# control-surface-right.net
KiCad netlist of a schematic drawn in EAGLE
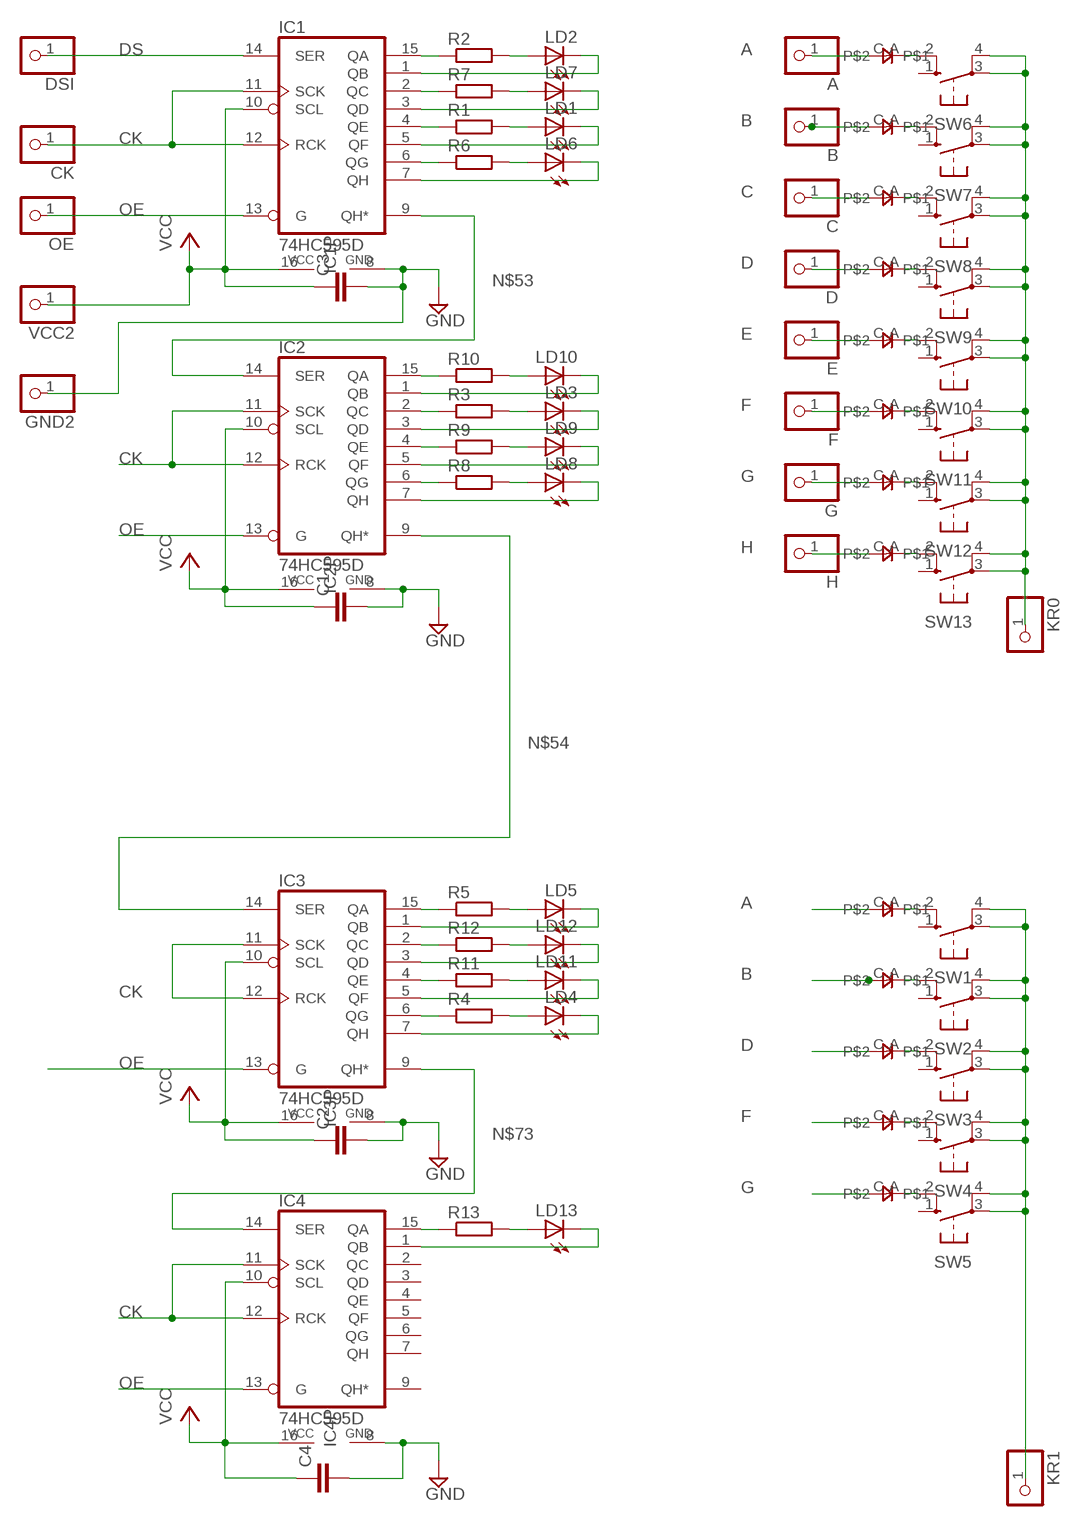
[diagram p0: schematic, sheet 1]

(export (version "E")
  (design (tool "Eeschema 10.0.6"))
  (components
    (comp (ref "A")
      (value "PINHD-1X1")
      (footprint "eagle-import:1X01")
      (libsource (lib "eagle-import") (part "PINHD-1X1"))
    )
    (comp (ref "B")
      (value "PINHD-1X1")
      (footprint "eagle-import:1X01")
      (libsource (lib "eagle-import") (part "PINHD-1X1"))
    )
    (comp (ref "C")
      (value "PINHD-1X1")
      (footprint "eagle-import:1X01")
      (libsource (lib "eagle-import") (part "PINHD-1X1"))
    )
    (comp (ref "C1")
      (value "C-EUC0805")
      (footprint "eagle-import:C0805")
      (libsource (lib "eagle-import") (part "C-EUC0805"))
    )
    (comp (ref "C2")
      (value "C-EUC0805")
      (footprint "eagle-import:C0805")
      (libsource (lib "eagle-import") (part "C-EUC0805"))
    )
    (comp (ref "C3")
      (value "C-EUC0805")
      (footprint "eagle-import:C0805")
      (libsource (lib "eagle-import") (part "C-EUC0805"))
    )
    (comp (ref "C4")
      (value "C-EUC0805")
      (footprint "eagle-import:C0805")
      (libsource (lib "eagle-import") (part "C-EUC0805"))
    )
    (comp (ref "CK")
      (value "PINHD-1X1")
      (footprint "eagle-import:1X01")
      (libsource (lib "eagle-import") (part "PINHD-1X1"))
    )
    (comp (ref "D")
      (value "PINHD-1X1")
      (footprint "eagle-import:1X01")
      (libsource (lib "eagle-import") (part "PINHD-1X1"))
    )
    (comp (ref "D1")
      (value "0805DIODE")
      (footprint "eagle-import:0805DIODE")
      (libsource (lib "eagle-import") (part "0805DIODE"))
    )
    (comp (ref "D2")
      (value "0805DIODE")
      (footprint "eagle-import:0805DIODE")
      (libsource (lib "eagle-import") (part "0805DIODE"))
    )
    (comp (ref "D3")
      (value "0805DIODE")
      (footprint "eagle-import:0805DIODE")
      (libsource (lib "eagle-import") (part "0805DIODE"))
    )
    (comp (ref "D4")
      (value "0805DIODE")
      (footprint "eagle-import:0805DIODE")
      (libsource (lib "eagle-import") (part "0805DIODE"))
    )
    (comp (ref "D5")
      (value "0805DIODE")
      (footprint "eagle-import:0805DIODE")
      (libsource (lib "eagle-import") (part "0805DIODE"))
    )
    (comp (ref "D6")
      (value "0805DIODE")
      (footprint "eagle-import:0805DIODE")
      (libsource (lib "eagle-import") (part "0805DIODE"))
    )
    (comp (ref "D7")
      (value "0805DIODE")
      (footprint "eagle-import:0805DIODE")
      (libsource (lib "eagle-import") (part "0805DIODE"))
    )
    (comp (ref "D8")
      (value "0805DIODE")
      (footprint "eagle-import:0805DIODE")
      (libsource (lib "eagle-import") (part "0805DIODE"))
    )
    (comp (ref "D9")
      (value "0805DIODE")
      (footprint "eagle-import:0805DIODE")
      (libsource (lib "eagle-import") (part "0805DIODE"))
    )
    (comp (ref "D10")
      (value "0805DIODE")
      (footprint "eagle-import:0805DIODE")
      (libsource (lib "eagle-import") (part "0805DIODE"))
    )
    (comp (ref "D11")
      (value "0805DIODE")
      (footprint "eagle-import:0805DIODE")
      (libsource (lib "eagle-import") (part "0805DIODE"))
    )
    (comp (ref "D12")
      (value "0805DIODE")
      (footprint "eagle-import:0805DIODE")
      (libsource (lib "eagle-import") (part "0805DIODE"))
    )
    (comp (ref "D13")
      (value "0805DIODE")
      (footprint "eagle-import:0805DIODE")
      (libsource (lib "eagle-import") (part "0805DIODE"))
    )
    (comp (ref "DSI")
      (value "PINHD-1X1")
      (footprint "eagle-import:1X01")
      (libsource (lib "eagle-import") (part "PINHD-1X1"))
    )
    (comp (ref "E")
      (value "PINHD-1X1")
      (footprint "eagle-import:1X01")
      (libsource (lib "eagle-import") (part "PINHD-1X1"))
    )
    (comp (ref "F")
      (value "PINHD-1X1")
      (footprint "eagle-import:1X01")
      (libsource (lib "eagle-import") (part "PINHD-1X1"))
    )
    (comp (ref "G")
      (value "PINHD-1X1")
      (footprint "eagle-import:1X01")
      (libsource (lib "eagle-import") (part "PINHD-1X1"))
    )
    (comp (ref "GND2")
      (value "PINHD-1X1")
      (footprint "eagle-import:1X01")
      (libsource (lib "eagle-import") (part "PINHD-1X1"))
    )
    (comp (ref "H")
      (value "PINHD-1X1")
      (footprint "eagle-import:1X01")
      (libsource (lib "eagle-import") (part "PINHD-1X1"))
    )
    (comp (ref "IC1")
      (value "74HC595D")
      (footprint "eagle-import:SO16")
      (libsource (lib "eagle-import") (part "74595DHC"))
    )
    (comp (ref "IC2")
      (value "74HC595D")
      (footprint "eagle-import:SO16")
      (libsource (lib "eagle-import") (part "74595DHC"))
    )
    (comp (ref "IC3")
      (value "74HC595D")
      (footprint "eagle-import:SO16")
      (libsource (lib "eagle-import") (part "74595DHC"))
    )
    (comp (ref "IC4")
      (value "74HC595D")
      (footprint "eagle-import:SO16")
      (libsource (lib "eagle-import") (part "74595DHC"))
    )
    (comp (ref "KR0")
      (value "PINHD-1X1")
      (footprint "eagle-import:1X01")
      (libsource (lib "eagle-import") (part "PINHD-1X1"))
    )
    (comp (ref "KR1")
      (value "PINHD-1X1")
      (footprint "eagle-import:1X01")
      (libsource (lib "eagle-import") (part "PINHD-1X1"))
    )
    (comp (ref "LD1")
      (value "LED3MM")
      (footprint "eagle-import:LED3MM")
      (libsource (lib "eagle-import") (part "LED3MM"))
    )
    (comp (ref "LD2")
      (value "LED3MM")
      (footprint "eagle-import:LED3MM")
      (libsource (lib "eagle-import") (part "LED3MM"))
    )
    (comp (ref "LD3")
      (value "LED3MM")
      (footprint "eagle-import:LED3MM")
      (libsource (lib "eagle-import") (part "LED3MM"))
    )
    (comp (ref "LD4")
      (value "LED3MM")
      (footprint "eagle-import:LED3MM")
      (libsource (lib "eagle-import") (part "LED3MM"))
    )
    (comp (ref "LD5")
      (value "LED3MM")
      (footprint "eagle-import:LED3MM")
      (libsource (lib "eagle-import") (part "LED3MM"))
    )
    (comp (ref "LD6")
      (value "LED3MM")
      (footprint "eagle-import:LED3MM")
      (libsource (lib "eagle-import") (part "LED3MM"))
    )
    (comp (ref "LD7")
      (value "LED3MM")
      (footprint "eagle-import:LED3MM")
      (libsource (lib "eagle-import") (part "LED3MM"))
    )
    (comp (ref "LD8")
      (value "LED3MM")
      (footprint "eagle-import:LED3MM")
      (libsource (lib "eagle-import") (part "LED3MM"))
    )
    (comp (ref "LD9")
      (value "LED3MM")
      (footprint "eagle-import:LED3MM")
      (libsource (lib "eagle-import") (part "LED3MM"))
    )
    (comp (ref "LD10")
      (value "LED3MM")
      (footprint "eagle-import:LED3MM")
      (libsource (lib "eagle-import") (part "LED3MM"))
    )
    (comp (ref "LD11")
      (value "LED3MM")
      (footprint "eagle-import:LED3MM")
      (libsource (lib "eagle-import") (part "LED3MM"))
    )
    (comp (ref "LD12")
      (value "LED3MM")
      (footprint "eagle-import:LED3MM")
      (libsource (lib "eagle-import") (part "LED3MM"))
    )
    (comp (ref "LD13")
      (value "LED3MM")
      (footprint "eagle-import:LED3MM")
      (libsource (lib "eagle-import") (part "LED3MM"))
    )
    (comp (ref "OE")
      (value "PINHD-1X1")
      (footprint "eagle-import:1X01")
      (libsource (lib "eagle-import") (part "PINHD-1X1"))
    )
    (comp (ref "R1")
      (value "R-EU_R0805")
      (footprint "eagle-import:R0805")
      (libsource (lib "eagle-import") (part "R-EU_R0805"))
    )
    (comp (ref "R2")
      (value "R-EU_R0805")
      (footprint "eagle-import:R0805")
      (libsource (lib "eagle-import") (part "R-EU_R0805"))
    )
    (comp (ref "R3")
      (value "R-EU_R0805")
      (footprint "eagle-import:R0805")
      (libsource (lib "eagle-import") (part "R-EU_R0805"))
    )
    (comp (ref "R4")
      (value "R-EU_R0805")
      (footprint "eagle-import:R0805")
      (libsource (lib "eagle-import") (part "R-EU_R0805"))
    )
    (comp (ref "R5")
      (value "R-EU_R0805")
      (footprint "eagle-import:R0805")
      (libsource (lib "eagle-import") (part "R-EU_R0805"))
    )
    (comp (ref "R6")
      (value "R-EU_R0805")
      (footprint "eagle-import:R0805")
      (libsource (lib "eagle-import") (part "R-EU_R0805"))
    )
    (comp (ref "R7")
      (value "R-EU_R0805")
      (footprint "eagle-import:R0805")
      (libsource (lib "eagle-import") (part "R-EU_R0805"))
    )
    (comp (ref "R8")
      (value "R-EU_R0805")
      (footprint "eagle-import:R0805")
      (libsource (lib "eagle-import") (part "R-EU_R0805"))
    )
    (comp (ref "R9")
      (value "R-EU_R0805")
      (footprint "eagle-import:R0805")
      (libsource (lib "eagle-import") (part "R-EU_R0805"))
    )
    (comp (ref "R10")
      (value "R-EU_R0805")
      (footprint "eagle-import:R0805")
      (libsource (lib "eagle-import") (part "R-EU_R0805"))
    )
    (comp (ref "R11")
      (value "R-EU_R0805")
      (footprint "eagle-import:R0805")
      (libsource (lib "eagle-import") (part "R-EU_R0805"))
    )
    (comp (ref "R12")
      (value "R-EU_R0805")
      (footprint "eagle-import:R0805")
      (libsource (lib "eagle-import") (part "R-EU_R0805"))
    )
    (comp (ref "R13")
      (value "R-EU_R0805")
      (footprint "eagle-import:R0805")
      (libsource (lib "eagle-import") (part "R-EU_R0805"))
    )
    (comp (ref "SW1")
      (value "40-XX")
      (footprint "eagle-import:B3F-40XX")
      (fields (field (name "MF") "OMRON COMPONENTS USA") (field (name "MPN") "B3F-4000"))
      (libsource (lib "eagle-import") (part "40-XX"))
    )
    (comp (ref "SW2")
      (value "40-XX")
      (footprint "eagle-import:B3F-40XX")
      (fields (field (name "MF") "OMRON COMPONENTS USA") (field (name "MPN") "B3F-4000"))
      (libsource (lib "eagle-import") (part "40-XX"))
    )
    (comp (ref "SW3")
      (value "40-XX")
      (footprint "eagle-import:B3F-40XX")
      (fields (field (name "MF") "OMRON COMPONENTS USA") (field (name "MPN") "B3F-4000"))
      (libsource (lib "eagle-import") (part "40-XX"))
    )
    (comp (ref "SW4")
      (value "40-XX")
      (footprint "eagle-import:B3F-40XX")
      (fields (field (name "MF") "OMRON COMPONENTS USA") (field (name "MPN") "B3F-4000"))
      (libsource (lib "eagle-import") (part "40-XX"))
    )
    (comp (ref "SW5")
      (value "40-XX")
      (footprint "eagle-import:B3F-40XX")
      (fields (field (name "MF") "OMRON COMPONENTS USA") (field (name "MPN") "B3F-4000"))
      (libsource (lib "eagle-import") (part "40-XX"))
    )
    (comp (ref "SW6")
      (value "40-XX")
      (footprint "eagle-import:B3F-40XX")
      (fields (field (name "MF") "OMRON COMPONENTS USA") (field (name "MPN") "B3F-4000"))
      (libsource (lib "eagle-import") (part "40-XX"))
    )
    (comp (ref "SW7")
      (value "40-XX")
      (footprint "eagle-import:B3F-40XX")
      (fields (field (name "MF") "OMRON COMPONENTS USA") (field (name "MPN") "B3F-4000"))
      (libsource (lib "eagle-import") (part "40-XX"))
    )
    (comp (ref "SW8")
      (value "40-XX")
      (footprint "eagle-import:B3F-40XX")
      (fields (field (name "MF") "OMRON COMPONENTS USA") (field (name "MPN") "B3F-4000"))
      (libsource (lib "eagle-import") (part "40-XX"))
    )
    (comp (ref "SW9")
      (value "40-XX")
      (footprint "eagle-import:B3F-40XX")
      (fields (field (name "MF") "OMRON COMPONENTS USA") (field (name "MPN") "B3F-4000"))
      (libsource (lib "eagle-import") (part "40-XX"))
    )
    (comp (ref "SW10")
      (value "40-XX")
      (footprint "eagle-import:B3F-40XX")
      (fields (field (name "MF") "OMRON COMPONENTS USA") (field (name "MPN") "B3F-4000"))
      (libsource (lib "eagle-import") (part "40-XX"))
    )
    (comp (ref "SW11")
      (value "40-XX")
      (footprint "eagle-import:B3F-40XX")
      (fields (field (name "MF") "OMRON COMPONENTS USA") (field (name "MPN") "B3F-4000"))
      (libsource (lib "eagle-import") (part "40-XX"))
    )
    (comp (ref "SW12")
      (value "40-XX")
      (footprint "eagle-import:B3F-40XX")
      (fields (field (name "MF") "OMRON COMPONENTS USA") (field (name "MPN") "B3F-4000"))
      (libsource (lib "eagle-import") (part "40-XX"))
    )
    (comp (ref "SW13")
      (value "40-XX")
      (footprint "eagle-import:B3F-40XX")
      (fields (field (name "MF") "OMRON COMPONENTS USA") (field (name "MPN") "B3F-4000"))
      (libsource (lib "eagle-import") (part "40-XX"))
    )
    (comp (ref "VCC2")
      (value "PINHD-1X1")
      (footprint "eagle-import:1X01")
      (libsource (lib "eagle-import") (part "PINHD-1X1"))
    )
  )
  (nets
    (net (code "1") (name "/A") (class "Default")
      (node (ref "A") (pin "1") (pinfunction "1_1") (pintype "passive"))
      (node (ref "D1") (pin "C") (pinfunction "P$1_C") (pintype "bidirectional"))
      (node (ref "D6") (pin "C") (pinfunction "P$1_C") (pintype "bidirectional"))
    )
    (net (code "2") (name "/B") (class "Default")
      (node (ref "B") (pin "1") (pinfunction "1_1") (pintype "passive"))
      (node (ref "D2") (pin "C") (pinfunction "P$1_C") (pintype "bidirectional"))
      (node (ref "D7") (pin "C") (pinfunction "P$1_C") (pintype "bidirectional"))
    )
    (net (code "3") (name "/C") (class "Default")
      (node (ref "C") (pin "1") (pinfunction "1_1") (pintype "passive"))
      (node (ref "D8") (pin "C") (pinfunction "P$1_C") (pintype "bidirectional"))
    )
    (net (code "4") (name "/CK") (class "Default")
      (node (ref "CK") (pin "1") (pinfunction "1_1") (pintype "passive"))
      (node (ref "IC1") (pin "11") (pinfunction "SCK_11") (pintype "input"))
      (node (ref "IC1") (pin "12") (pinfunction "RCK_12") (pintype "input"))
      (node (ref "IC2") (pin "11") (pinfunction "SCK_11") (pintype "input"))
      (node (ref "IC2") (pin "12") (pinfunction "RCK_12") (pintype "input"))
      (node (ref "IC3") (pin "11") (pinfunction "SCK_11") (pintype "input"))
      (node (ref "IC3") (pin "12") (pinfunction "RCK_12") (pintype "input"))
      (node (ref "IC4") (pin "11") (pinfunction "SCK_11") (pintype "input"))
      (node (ref "IC4") (pin "12") (pinfunction "RCK_12") (pintype "input"))
    )
    (net (code "5") (name "/D") (class "Default")
      (node (ref "D") (pin "1") (pinfunction "1_1") (pintype "passive"))
      (node (ref "D3") (pin "C") (pinfunction "P$1_C") (pintype "bidirectional"))
      (node (ref "D9") (pin "C") (pinfunction "P$1_C") (pintype "bidirectional"))
    )
    (net (code "6") (name "/DS") (class "Default")
      (node (ref "DSI") (pin "1") (pinfunction "1_1") (pintype "passive"))
      (node (ref "IC1") (pin "14") (pinfunction "SER_14") (pintype "input"))
    )
    (net (code "7") (name "/E") (class "Default")
      (node (ref "D10") (pin "C") (pinfunction "P$1_C") (pintype "bidirectional"))
      (node (ref "E") (pin "1") (pinfunction "1_1") (pintype "passive"))
    )
    (net (code "8") (name "/F") (class "Default")
      (node (ref "D11") (pin "C") (pinfunction "P$1_C") (pintype "bidirectional"))
      (node (ref "D4") (pin "C") (pinfunction "P$1_C") (pintype "bidirectional"))
      (node (ref "F") (pin "1") (pinfunction "1_1") (pintype "passive"))
    )
    (net (code "9") (name "/G") (class "Default")
      (node (ref "D12") (pin "C") (pinfunction "P$1_C") (pintype "bidirectional"))
      (node (ref "D5") (pin "C") (pinfunction "P$1_C") (pintype "bidirectional"))
      (node (ref "G") (pin "1") (pinfunction "1_1") (pintype "passive"))
    )
    (net (code "10") (name "/H") (class "Default")
      (node (ref "D13") (pin "C") (pinfunction "P$1_C") (pintype "bidirectional"))
      (node (ref "H") (pin "1") (pinfunction "1_1") (pintype "passive"))
    )
    (net (code "11") (name "/N$53") (class "Default")
      (node (ref "IC1") (pin "9") (pinfunction "QH*_9") (pintype "tri_state"))
      (node (ref "IC2") (pin "14") (pinfunction "SER_14") (pintype "input"))
    )
    (net (code "12") (name "/N$54") (class "Default")
      (node (ref "IC2") (pin "9") (pinfunction "QH*_9") (pintype "tri_state"))
      (node (ref "IC3") (pin "14") (pinfunction "SER_14") (pintype "input"))
    )
    (net (code "13") (name "/N$73") (class "Default")
      (node (ref "IC3") (pin "9") (pinfunction "QH*_9") (pintype "tri_state"))
      (node (ref "IC4") (pin "14") (pinfunction "SER_14") (pintype "input"))
    )
    (net (code "14") (name "/OE") (class "Default")
      (node (ref "IC1") (pin "13") (pinfunction "G_13") (pintype "input"))
      (node (ref "IC2") (pin "13") (pinfunction "G_13") (pintype "input"))
      (node (ref "IC3") (pin "13") (pinfunction "G_13") (pintype "input"))
      (node (ref "IC4") (pin "13") (pinfunction "G_13") (pintype "input"))
      (node (ref "OE") (pin "1") (pinfunction "1_1") (pintype "passive"))
    )
    (net (code "15") (name "GND") (class "Default")
      (node (ref "C1") (pin "2") (pinfunction "2_2") (pintype "passive"))
      (node (ref "C2") (pin "2") (pinfunction "2_2") (pintype "passive"))
      (node (ref "C3") (pin "2") (pinfunction "2_2") (pintype "passive"))
      (node (ref "C4") (pin "2") (pinfunction "2_2") (pintype "passive"))
      (node (ref "GND2") (pin "1") (pinfunction "1_1") (pintype "passive"))
      (node (ref "IC1") (pin "8") (pinfunction "GND_8") (pintype "power_in"))
      (node (ref "IC2") (pin "8") (pinfunction "GND_8") (pintype "power_in"))
      (node (ref "IC3") (pin "8") (pinfunction "GND_8") (pintype "power_in"))
      (node (ref "IC4") (pin "8") (pinfunction "GND_8") (pintype "power_in"))
    )
    (net (code "16") (name "Net-(D1-P$2)") (class "Default")
      (node (ref "D1") (pin "A") (pinfunction "P$2_A") (pintype "bidirectional"))
      (node (ref "SW1") (pin "2") (pinfunction "S1_2") (pintype "passive"))
    )
    (net (code "17") (name "Net-(D2-P$2)") (class "Default")
      (node (ref "D2") (pin "A") (pinfunction "P$2_A") (pintype "bidirectional"))
      (node (ref "SW2") (pin "2") (pinfunction "S1_2") (pintype "passive"))
    )
    (net (code "18") (name "Net-(D3-P$2)") (class "Default")
      (node (ref "D3") (pin "A") (pinfunction "P$2_A") (pintype "bidirectional"))
      (node (ref "SW3") (pin "2") (pinfunction "S1_2") (pintype "passive"))
    )
    (net (code "19") (name "Net-(D4-P$2)") (class "Default")
      (node (ref "D4") (pin "A") (pinfunction "P$2_A") (pintype "bidirectional"))
      (node (ref "SW4") (pin "2") (pinfunction "S1_2") (pintype "passive"))
    )
    (net (code "20") (name "Net-(D5-P$2)") (class "Default")
      (node (ref "D5") (pin "A") (pinfunction "P$2_A") (pintype "bidirectional"))
      (node (ref "SW5") (pin "2") (pinfunction "S1_2") (pintype "passive"))
    )
    (net (code "21") (name "Net-(D6-P$2)") (class "Default")
      (node (ref "D6") (pin "A") (pinfunction "P$2_A") (pintype "bidirectional"))
      (node (ref "SW6") (pin "2") (pinfunction "S1_2") (pintype "passive"))
    )
    (net (code "22") (name "Net-(D7-P$2)") (class "Default")
      (node (ref "D7") (pin "A") (pinfunction "P$2_A") (pintype "bidirectional"))
      (node (ref "SW7") (pin "2") (pinfunction "S1_2") (pintype "passive"))
    )
    (net (code "23") (name "Net-(D8-P$2)") (class "Default")
      (node (ref "D8") (pin "A") (pinfunction "P$2_A") (pintype "bidirectional"))
      (node (ref "SW8") (pin "2") (pinfunction "S1_2") (pintype "passive"))
    )
    (net (code "24") (name "Net-(D9-P$2)") (class "Default")
      (node (ref "D9") (pin "A") (pinfunction "P$2_A") (pintype "bidirectional"))
      (node (ref "SW9") (pin "2") (pinfunction "S1_2") (pintype "passive"))
    )
    (net (code "25") (name "Net-(D10-P$2)") (class "Default")
      (node (ref "D10") (pin "A") (pinfunction "P$2_A") (pintype "bidirectional"))
      (node (ref "SW10") (pin "2") (pinfunction "S1_2") (pintype "passive"))
    )
    (net (code "26") (name "Net-(D11-P$2)") (class "Default")
      (node (ref "D11") (pin "A") (pinfunction "P$2_A") (pintype "bidirectional"))
      (node (ref "SW11") (pin "2") (pinfunction "S1_2") (pintype "passive"))
    )
    (net (code "27") (name "Net-(D12-P$2)") (class "Default")
      (node (ref "D12") (pin "A") (pinfunction "P$2_A") (pintype "bidirectional"))
      (node (ref "SW12") (pin "2") (pinfunction "S1_2") (pintype "passive"))
    )
    (net (code "28") (name "Net-(D13-P$2)") (class "Default")
      (node (ref "D13") (pin "A") (pinfunction "P$2_A") (pintype "bidirectional"))
      (node (ref "SW13") (pin "2") (pinfunction "S1_2") (pintype "passive"))
    )
    (net (code "29") (name "Net-(IC1A-QA)") (class "Default")
      (node (ref "IC1") (pin "15") (pinfunction "QA_15") (pintype "tri_state"))
      (node (ref "R2") (pin "1") (pinfunction "1_1") (pintype "passive"))
    )
    (net (code "30") (name "Net-(IC1A-QB)") (class "Default")
      (node (ref "IC1") (pin "1") (pinfunction "QB_1") (pintype "tri_state"))
      (node (ref "LD2") (pin "K") (pinfunction "C_K") (pintype "passive"))
    )
    (net (code "31") (name "Net-(IC1A-QC)") (class "Default")
      (node (ref "IC1") (pin "2") (pinfunction "QC_2") (pintype "tri_state"))
      (node (ref "R7") (pin "1") (pinfunction "1_1") (pintype "passive"))
    )
    (net (code "32") (name "Net-(IC1A-QD)") (class "Default")
      (node (ref "IC1") (pin "3") (pinfunction "QD_3") (pintype "tri_state"))
      (node (ref "LD7") (pin "K") (pinfunction "C_K") (pintype "passive"))
    )
    (net (code "33") (name "Net-(IC1A-QE)") (class "Default")
      (node (ref "IC1") (pin "4") (pinfunction "QE_4") (pintype "tri_state"))
      (node (ref "R1") (pin "1") (pinfunction "1_1") (pintype "passive"))
    )
    (net (code "34") (name "Net-(IC1A-QF)") (class "Default")
      (node (ref "IC1") (pin "5") (pinfunction "QF_5") (pintype "tri_state"))
      (node (ref "LD1") (pin "K") (pinfunction "C_K") (pintype "passive"))
    )
    (net (code "35") (name "Net-(IC1A-QG)") (class "Default")
      (node (ref "IC1") (pin "6") (pinfunction "QG_6") (pintype "tri_state"))
      (node (ref "R6") (pin "1") (pinfunction "1_1") (pintype "passive"))
    )
    (net (code "36") (name "Net-(IC1A-QH)") (class "Default")
      (node (ref "IC1") (pin "7") (pinfunction "QH_7") (pintype "tri_state"))
      (node (ref "LD6") (pin "K") (pinfunction "C_K") (pintype "passive"))
    )
    (net (code "37") (name "Net-(IC2A-QA)") (class "Default")
      (node (ref "IC2") (pin "15") (pinfunction "QA_15") (pintype "tri_state"))
      (node (ref "R10") (pin "1") (pinfunction "1_1") (pintype "passive"))
    )
    (net (code "38") (name "Net-(IC2A-QB)") (class "Default")
      (node (ref "IC2") (pin "1") (pinfunction "QB_1") (pintype "tri_state"))
      (node (ref "LD10") (pin "K") (pinfunction "C_K") (pintype "passive"))
    )
    (net (code "39") (name "Net-(IC2A-QC)") (class "Default")
      (node (ref "IC2") (pin "2") (pinfunction "QC_2") (pintype "tri_state"))
      (node (ref "R3") (pin "1") (pinfunction "1_1") (pintype "passive"))
    )
    (net (code "40") (name "Net-(IC2A-QD)") (class "Default")
      (node (ref "IC2") (pin "3") (pinfunction "QD_3") (pintype "tri_state"))
      (node (ref "LD3") (pin "K") (pinfunction "C_K") (pintype "passive"))
    )
    (net (code "41") (name "Net-(IC2A-QE)") (class "Default")
      (node (ref "IC2") (pin "4") (pinfunction "QE_4") (pintype "tri_state"))
      (node (ref "R9") (pin "1") (pinfunction "1_1") (pintype "passive"))
    )
    (net (code "42") (name "Net-(IC2A-QF)") (class "Default")
      (node (ref "IC2") (pin "5") (pinfunction "QF_5") (pintype "tri_state"))
      (node (ref "LD9") (pin "K") (pinfunction "C_K") (pintype "passive"))
    )
    (net (code "43") (name "Net-(IC2A-QG)") (class "Default")
      (node (ref "IC2") (pin "6") (pinfunction "QG_6") (pintype "tri_state"))
      (node (ref "R8") (pin "1") (pinfunction "1_1") (pintype "passive"))
    )
    (net (code "44") (name "Net-(IC2A-QH)") (class "Default")
      (node (ref "IC2") (pin "7") (pinfunction "QH_7") (pintype "tri_state"))
      (node (ref "LD8") (pin "K") (pinfunction "C_K") (pintype "passive"))
    )
    (net (code "45") (name "Net-(IC3A-QA)") (class "Default")
      (node (ref "IC3") (pin "15") (pinfunction "QA_15") (pintype "tri_state"))
      (node (ref "R5") (pin "1") (pinfunction "1_1") (pintype "passive"))
    )
    (net (code "46") (name "Net-(IC3A-QB)") (class "Default")
      (node (ref "IC3") (pin "1") (pinfunction "QB_1") (pintype "tri_state"))
      (node (ref "LD5") (pin "K") (pinfunction "C_K") (pintype "passive"))
    )
    (net (code "47") (name "Net-(IC3A-QC)") (class "Default")
      (node (ref "IC3") (pin "2") (pinfunction "QC_2") (pintype "tri_state"))
      (node (ref "R12") (pin "1") (pinfunction "1_1") (pintype "passive"))
    )
    (net (code "48") (name "Net-(IC3A-QD)") (class "Default")
      (node (ref "IC3") (pin "3") (pinfunction "QD_3") (pintype "tri_state"))
      (node (ref "LD12") (pin "K") (pinfunction "C_K") (pintype "passive"))
    )
    (net (code "49") (name "Net-(IC3A-QE)") (class "Default")
      (node (ref "IC3") (pin "4") (pinfunction "QE_4") (pintype "tri_state"))
      (node (ref "R11") (pin "1") (pinfunction "1_1") (pintype "passive"))
    )
    (net (code "50") (name "Net-(IC3A-QF)") (class "Default")
      (node (ref "IC3") (pin "5") (pinfunction "QF_5") (pintype "tri_state"))
      (node (ref "LD11") (pin "K") (pinfunction "C_K") (pintype "passive"))
    )
    (net (code "51") (name "Net-(IC3A-QG)") (class "Default")
      (node (ref "IC3") (pin "6") (pinfunction "QG_6") (pintype "tri_state"))
      (node (ref "R4") (pin "1") (pinfunction "1_1") (pintype "passive"))
    )
    (net (code "52") (name "Net-(IC3A-QH)") (class "Default")
      (node (ref "IC3") (pin "7") (pinfunction "QH_7") (pintype "tri_state"))
      (node (ref "LD4") (pin "K") (pinfunction "C_K") (pintype "passive"))
    )
    (net (code "53") (name "Net-(IC4A-QA)") (class "Default")
      (node (ref "IC4") (pin "15") (pinfunction "QA_15") (pintype "tri_state"))
      (node (ref "R13") (pin "1") (pinfunction "1_1") (pintype "passive"))
    )
    (net (code "54") (name "Net-(IC4A-QB)") (class "Default")
      (node (ref "IC4") (pin "1") (pinfunction "QB_1") (pintype "tri_state"))
      (node (ref "LD13") (pin "K") (pinfunction "C_K") (pintype "passive"))
    )
    (net (code "55") (name "Net-(LD1-PadA)") (class "Default")
      (node (ref "LD1") (pin "A") (pinfunction "A_A") (pintype "passive"))
      (node (ref "R1") (pin "2") (pinfunction "2_2") (pintype "passive"))
    )
    (net (code "56") (name "Net-(LD2-PadA)") (class "Default")
      (node (ref "LD2") (pin "A") (pinfunction "A_A") (pintype "passive"))
      (node (ref "R2") (pin "2") (pinfunction "2_2") (pintype "passive"))
    )
    (net (code "57") (name "Net-(LD3-PadA)") (class "Default")
      (node (ref "LD3") (pin "A") (pinfunction "A_A") (pintype "passive"))
      (node (ref "R3") (pin "2") (pinfunction "2_2") (pintype "passive"))
    )
    (net (code "58") (name "Net-(LD4-PadA)") (class "Default")
      (node (ref "LD4") (pin "A") (pinfunction "A_A") (pintype "passive"))
      (node (ref "R4") (pin "2") (pinfunction "2_2") (pintype "passive"))
    )
    (net (code "59") (name "Net-(LD5-PadA)") (class "Default")
      (node (ref "LD5") (pin "A") (pinfunction "A_A") (pintype "passive"))
      (node (ref "R5") (pin "2") (pinfunction "2_2") (pintype "passive"))
    )
    (net (code "60") (name "Net-(LD6-PadA)") (class "Default")
      (node (ref "LD6") (pin "A") (pinfunction "A_A") (pintype "passive"))
      (node (ref "R6") (pin "2") (pinfunction "2_2") (pintype "passive"))
    )
    (net (code "61") (name "Net-(LD7-PadA)") (class "Default")
      (node (ref "LD7") (pin "A") (pinfunction "A_A") (pintype "passive"))
      (node (ref "R7") (pin "2") (pinfunction "2_2") (pintype "passive"))
    )
    (net (code "62") (name "Net-(LD8-PadA)") (class "Default")
      (node (ref "LD8") (pin "A") (pinfunction "A_A") (pintype "passive"))
      (node (ref "R8") (pin "2") (pinfunction "2_2") (pintype "passive"))
    )
    (net (code "63") (name "Net-(LD9-PadA)") (class "Default")
      (node (ref "LD9") (pin "A") (pinfunction "A_A") (pintype "passive"))
      (node (ref "R9") (pin "2") (pinfunction "2_2") (pintype "passive"))
    )
    (net (code "64") (name "Net-(LD10-PadA)") (class "Default")
      (node (ref "LD10") (pin "A") (pinfunction "A_A") (pintype "passive"))
      (node (ref "R10") (pin "2") (pinfunction "2_2") (pintype "passive"))
    )
    (net (code "65") (name "Net-(LD11-PadA)") (class "Default")
      (node (ref "LD11") (pin "A") (pinfunction "A_A") (pintype "passive"))
      (node (ref "R11") (pin "2") (pinfunction "2_2") (pintype "passive"))
    )
    (net (code "66") (name "Net-(LD12-PadA)") (class "Default")
      (node (ref "LD12") (pin "A") (pinfunction "A_A") (pintype "passive"))
      (node (ref "R12") (pin "2") (pinfunction "2_2") (pintype "passive"))
    )
    (net (code "67") (name "Net-(LD13-PadA)") (class "Default")
      (node (ref "LD13") (pin "A") (pinfunction "A_A") (pintype "passive"))
      (node (ref "R13") (pin "2") (pinfunction "2_2") (pintype "passive"))
    )
    (net (code "68") (name "Net-(SW1-P)") (class "Default")
      (node (ref "KR1") (pin "1") (pinfunction "1_1") (pintype "passive"))
      (node (ref "SW1") (pin "3") (pinfunction "P_3") (pintype "passive"))
      (node (ref "SW1") (pin "4") (pinfunction "P1_4") (pintype "passive"))
      (node (ref "SW2") (pin "3") (pinfunction "P_3") (pintype "passive"))
      (node (ref "SW2") (pin "4") (pinfunction "P1_4") (pintype "passive"))
      (node (ref "SW3") (pin "3") (pinfunction "P_3") (pintype "passive"))
      (node (ref "SW3") (pin "4") (pinfunction "P1_4") (pintype "passive"))
      (node (ref "SW4") (pin "3") (pinfunction "P_3") (pintype "passive"))
      (node (ref "SW4") (pin "4") (pinfunction "P1_4") (pintype "passive"))
      (node (ref "SW5") (pin "3") (pinfunction "P_3") (pintype "passive"))
      (node (ref "SW5") (pin "4") (pinfunction "P1_4") (pintype "passive"))
    )
    (net (code "69") (name "Net-(SW10-P)") (class "Default")
      (node (ref "KR0") (pin "1") (pinfunction "1_1") (pintype "passive"))
      (node (ref "SW10") (pin "3") (pinfunction "P_3") (pintype "passive"))
      (node (ref "SW10") (pin "4") (pinfunction "P1_4") (pintype "passive"))
      (node (ref "SW11") (pin "3") (pinfunction "P_3") (pintype "passive"))
      (node (ref "SW11") (pin "4") (pinfunction "P1_4") (pintype "passive"))
      (node (ref "SW12") (pin "3") (pinfunction "P_3") (pintype "passive"))
      (node (ref "SW12") (pin "4") (pinfunction "P1_4") (pintype "passive"))
      (node (ref "SW13") (pin "3") (pinfunction "P_3") (pintype "passive"))
      (node (ref "SW13") (pin "4") (pinfunction "P1_4") (pintype "passive"))
      (node (ref "SW6") (pin "3") (pinfunction "P_3") (pintype "passive"))
      (node (ref "SW6") (pin "4") (pinfunction "P1_4") (pintype "passive"))
      (node (ref "SW7") (pin "3") (pinfunction "P_3") (pintype "passive"))
      (node (ref "SW7") (pin "4") (pinfunction "P1_4") (pintype "passive"))
      (node (ref "SW8") (pin "3") (pinfunction "P_3") (pintype "passive"))
      (node (ref "SW8") (pin "4") (pinfunction "P1_4") (pintype "passive"))
      (node (ref "SW9") (pin "3") (pinfunction "P_3") (pintype "passive"))
      (node (ref "SW9") (pin "4") (pinfunction "P1_4") (pintype "passive"))
    )
    (net (code "70") (name "VCC") (class "Default")
      (node (ref "C1") (pin "1") (pinfunction "1_1") (pintype "passive"))
      (node (ref "C2") (pin "1") (pinfunction "1_1") (pintype "passive"))
      (node (ref "C3") (pin "1") (pinfunction "1_1") (pintype "passive"))
      (node (ref "C4") (pin "1") (pinfunction "1_1") (pintype "passive"))
      (node (ref "IC1") (pin "10") (pinfunction "SCL_10") (pintype "input"))
      (node (ref "IC1") (pin "16") (pinfunction "VCC_16") (pintype "power_in"))
      (node (ref "IC2") (pin "10") (pinfunction "SCL_10") (pintype "input"))
      (node (ref "IC2") (pin "16") (pinfunction "VCC_16") (pintype "power_in"))
      (node (ref "IC3") (pin "10") (pinfunction "SCL_10") (pintype "input"))
      (node (ref "IC3") (pin "16") (pinfunction "VCC_16") (pintype "power_in"))
      (node (ref "IC4") (pin "10") (pinfunction "SCL_10") (pintype "input"))
      (node (ref "IC4") (pin "16") (pinfunction "VCC_16") (pintype "power_in"))
      (node (ref "VCC2") (pin "1") (pinfunction "1_1") (pintype "passive"))
    )
    (net (code "71") (name "unconnected-(IC4A-QC-Pad2)") (class "Default")
      (node (ref "IC4") (pin "2") (pinfunction "QC_2") (pintype "tri_state"))
    )
    (net (code "72") (name "unconnected-(IC4A-QD-Pad3)") (class "Default")
      (node (ref "IC4") (pin "3") (pinfunction "QD_3") (pintype "tri_state"))
    )
    (net (code "73") (name "unconnected-(IC4A-QE-Pad4)") (class "Default")
      (node (ref "IC4") (pin "4") (pinfunction "QE_4") (pintype "tri_state"))
    )
    (net (code "74") (name "unconnected-(IC4A-QF-Pad5)") (class "Default")
      (node (ref "IC4") (pin "5") (pinfunction "QF_5") (pintype "tri_state"))
    )
    (net (code "75") (name "unconnected-(IC4A-QG-Pad6)") (class "Default")
      (node (ref "IC4") (pin "6") (pinfunction "QG_6") (pintype "tri_state"))
    )
    (net (code "76") (name "unconnected-(IC4A-QH*-Pad9)") (class "Default")
      (node (ref "IC4") (pin "9") (pinfunction "QH*_9") (pintype "tri_state"))
    )
    (net (code "77") (name "unconnected-(IC4A-QH-Pad7)") (class "Default")
      (node (ref "IC4") (pin "7") (pinfunction "QH_7") (pintype "tri_state"))
    )
    (net (code "78") (name "unconnected-(SW1-S-Pad1)") (class "Default")
      (node (ref "SW1") (pin "1") (pinfunction "S_1") (pintype "passive"))
    )
    (net (code "79") (name "unconnected-(SW2-S-Pad1)") (class "Default")
      (node (ref "SW2") (pin "1") (pinfunction "S_1") (pintype "passive"))
    )
    (net (code "80") (name "unconnected-(SW3-S-Pad1)") (class "Default")
      (node (ref "SW3") (pin "1") (pinfunction "S_1") (pintype "passive"))
    )
    (net (code "81") (name "unconnected-(SW4-S-Pad1)") (class "Default")
      (node (ref "SW4") (pin "1") (pinfunction "S_1") (pintype "passive"))
    )
    (net (code "82") (name "unconnected-(SW5-S-Pad1)") (class "Default")
      (node (ref "SW5") (pin "1") (pinfunction "S_1") (pintype "passive"))
    )
    (net (code "83") (name "unconnected-(SW6-S-Pad1)") (class "Default")
      (node (ref "SW6") (pin "1") (pinfunction "S_1") (pintype "passive"))
    )
    (net (code "84") (name "unconnected-(SW7-S-Pad1)") (class "Default")
      (node (ref "SW7") (pin "1") (pinfunction "S_1") (pintype "passive"))
    )
    (net (code "85") (name "unconnected-(SW8-S-Pad1)") (class "Default")
      (node (ref "SW8") (pin "1") (pinfunction "S_1") (pintype "passive"))
    )
    (net (code "86") (name "unconnected-(SW9-S-Pad1)") (class "Default")
      (node (ref "SW9") (pin "1") (pinfunction "S_1") (pintype "passive"))
    )
    (net (code "87") (name "unconnected-(SW10-S-Pad1)") (class "Default")
      (node (ref "SW10") (pin "1") (pinfunction "S_1") (pintype "passive"))
    )
    (net (code "88") (name "unconnected-(SW11-S-Pad1)") (class "Default")
      (node (ref "SW11") (pin "1") (pinfunction "S_1") (pintype "passive"))
    )
    (net (code "89") (name "unconnected-(SW12-S-Pad1)") (class "Default")
      (node (ref "SW12") (pin "1") (pinfunction "S_1") (pintype "passive"))
    )
    (net (code "90") (name "unconnected-(SW13-S-Pad1)") (class "Default")
      (node (ref "SW13") (pin "1") (pinfunction "S_1") (pintype "passive"))
    )
  )
)
